# Power.net
KiCad netlist of a schematic drawn in Altium Designer
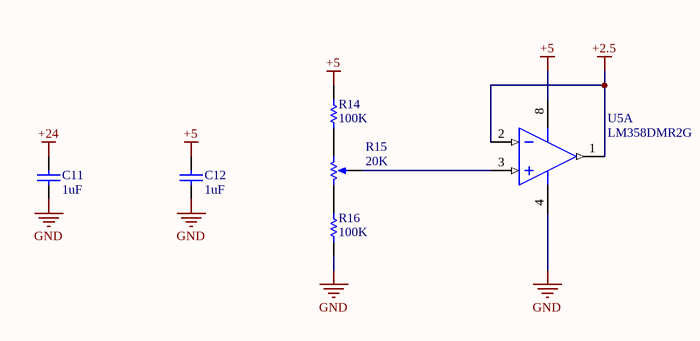
[diagram p0: Power.SchDoc]

(export (version "E")
  (design (tool "Eeschema 10.0.6"))
  (components
    (comp (ref "C11")
      (value "1uF")
      (footprint "CAPC1608X10M")
      (description "GRM188 0603(1.6mm*0.8mm) ±5% and ±10% (15pF-2.2uF) SMD Capacitor")
      (fields (field (name "PUBLISHER") "Altium Limited"))
      (libsource (lib "Acoustics") (part "GRM188"))
    )
    (comp (ref "C12")
      (value "1uF")
      (footprint "CAPC1608X10M")
      (description "GRM188 0603(1.6mm*0.8mm) ±5% and ±10% (15pF-2.2uF) SMD Capacitor")
      (fields (field (name "PUBLISHER") "Altium Limited"))
      (libsource (lib "Acoustics") (part "GRM188"))
    )
    (comp (ref "R14")
      (value "100K")
      (footprint "RESC1608X06M")
      (description "RC0603 JR-07 0603 (1.6mm*0.8mm) ±1% 1% (0R-4.7MR) chip resistor")
      (fields (field (name "PUBLISHER") "Altium Limited"))
      (libsource (lib "Frontend") (part "RC0603_JR07"))
    )
    (comp (ref "R15")
      (value "20K")
      (footprint "TC33X-1_BRN")
      (description "TRIMMER 20K OHM 0.1W J LEAD TOP")
      (fields (field (name "PUBLISHER") "Altium Limited"))
      (libsource (lib "Acoustics") (part "TC33X-1-203E"))
    )
    (comp (ref "R16")
      (value "100K")
      (footprint "RESC1608X06M")
      (description "RC0603 JR-07 0603 (1.6mm*0.8mm) ±1% 1% (0R-4.7MR) chip resistor")
      (fields (field (name "PUBLISHER") "Altium Limited"))
      (libsource (lib "Frontend") (part "RC0603_JR07"))
    )
    (comp (ref "U5")
      (value "LM358DMR2G")
      (footprint "ONSC-MICRO-8-846A-02_H_V")
      (fields (field (name "MANUFACTURER") "On Semiconductor"))
      (libsource (lib "Altium Content Vault") (part "ONSC-LM358_NCV2904-8"))
    )
  )
  (nets
    (net (code "1") (name "+2.5") (class "Default")
      (node (ref "U5") (pin "1") (pinfunction "OUTA_1") (pintype "output"))
      (node (ref "U5") (pin "2") (pinfunction "INA-_2") (pintype "input"))
    )
    (net (code "2") (name "+5") (class "Default")
      (node (ref "C12") (pin "2") (pinfunction "2_2") (pintype "passive"))
      (node (ref "R14") (pin "2") (pinfunction "2_2") (pintype "passive"))
      (node (ref "U5") (pin "8") (pinfunction "VCC_8") (pintype "power_in"))
    )
    (net (code "3") (name "+24") (class "Default")
      (node (ref "C11") (pin "2") (pinfunction "2_2") (pintype "passive"))
    )
    (net (code "4") (name "GND") (class "Default")
      (node (ref "C11") (pin "1") (pinfunction "1_1") (pintype "passive"))
      (node (ref "C12") (pin "1") (pinfunction "1_1") (pintype "passive"))
      (node (ref "R16") (pin "1") (pinfunction "1_1") (pintype "passive"))
      (node (ref "U5") (pin "4") (pinfunction "VEE/GND_4") (pintype "power_in"))
    )
    (net (code "5") (name "Net-(R15-BOT)") (class "Default")
      (node (ref "R15") (pin "2") (pinfunction "BOT_2") (pintype "passive"))
      (node (ref "R16") (pin "2") (pinfunction "2_2") (pintype "passive"))
    )
    (net (code "6") (name "Net-(R15-TAP)") (class "Default")
      (node (ref "R15") (pin "3") (pinfunction "TAP_3") (pintype "passive"))
      (node (ref "U5") (pin "3") (pinfunction "INA+_3") (pintype "input"))
    )
    (net (code "7") (name "Net-(R15-TOP)") (class "Default")
      (node (ref "R14") (pin "1") (pinfunction "1_1") (pintype "passive"))
      (node (ref "R15") (pin "1") (pinfunction "TOP_1") (pintype "passive"))
    )
  )
)
